# riffleito-KAP-REVB.net
KiCad netlist of a schematic drawn in EAGLE
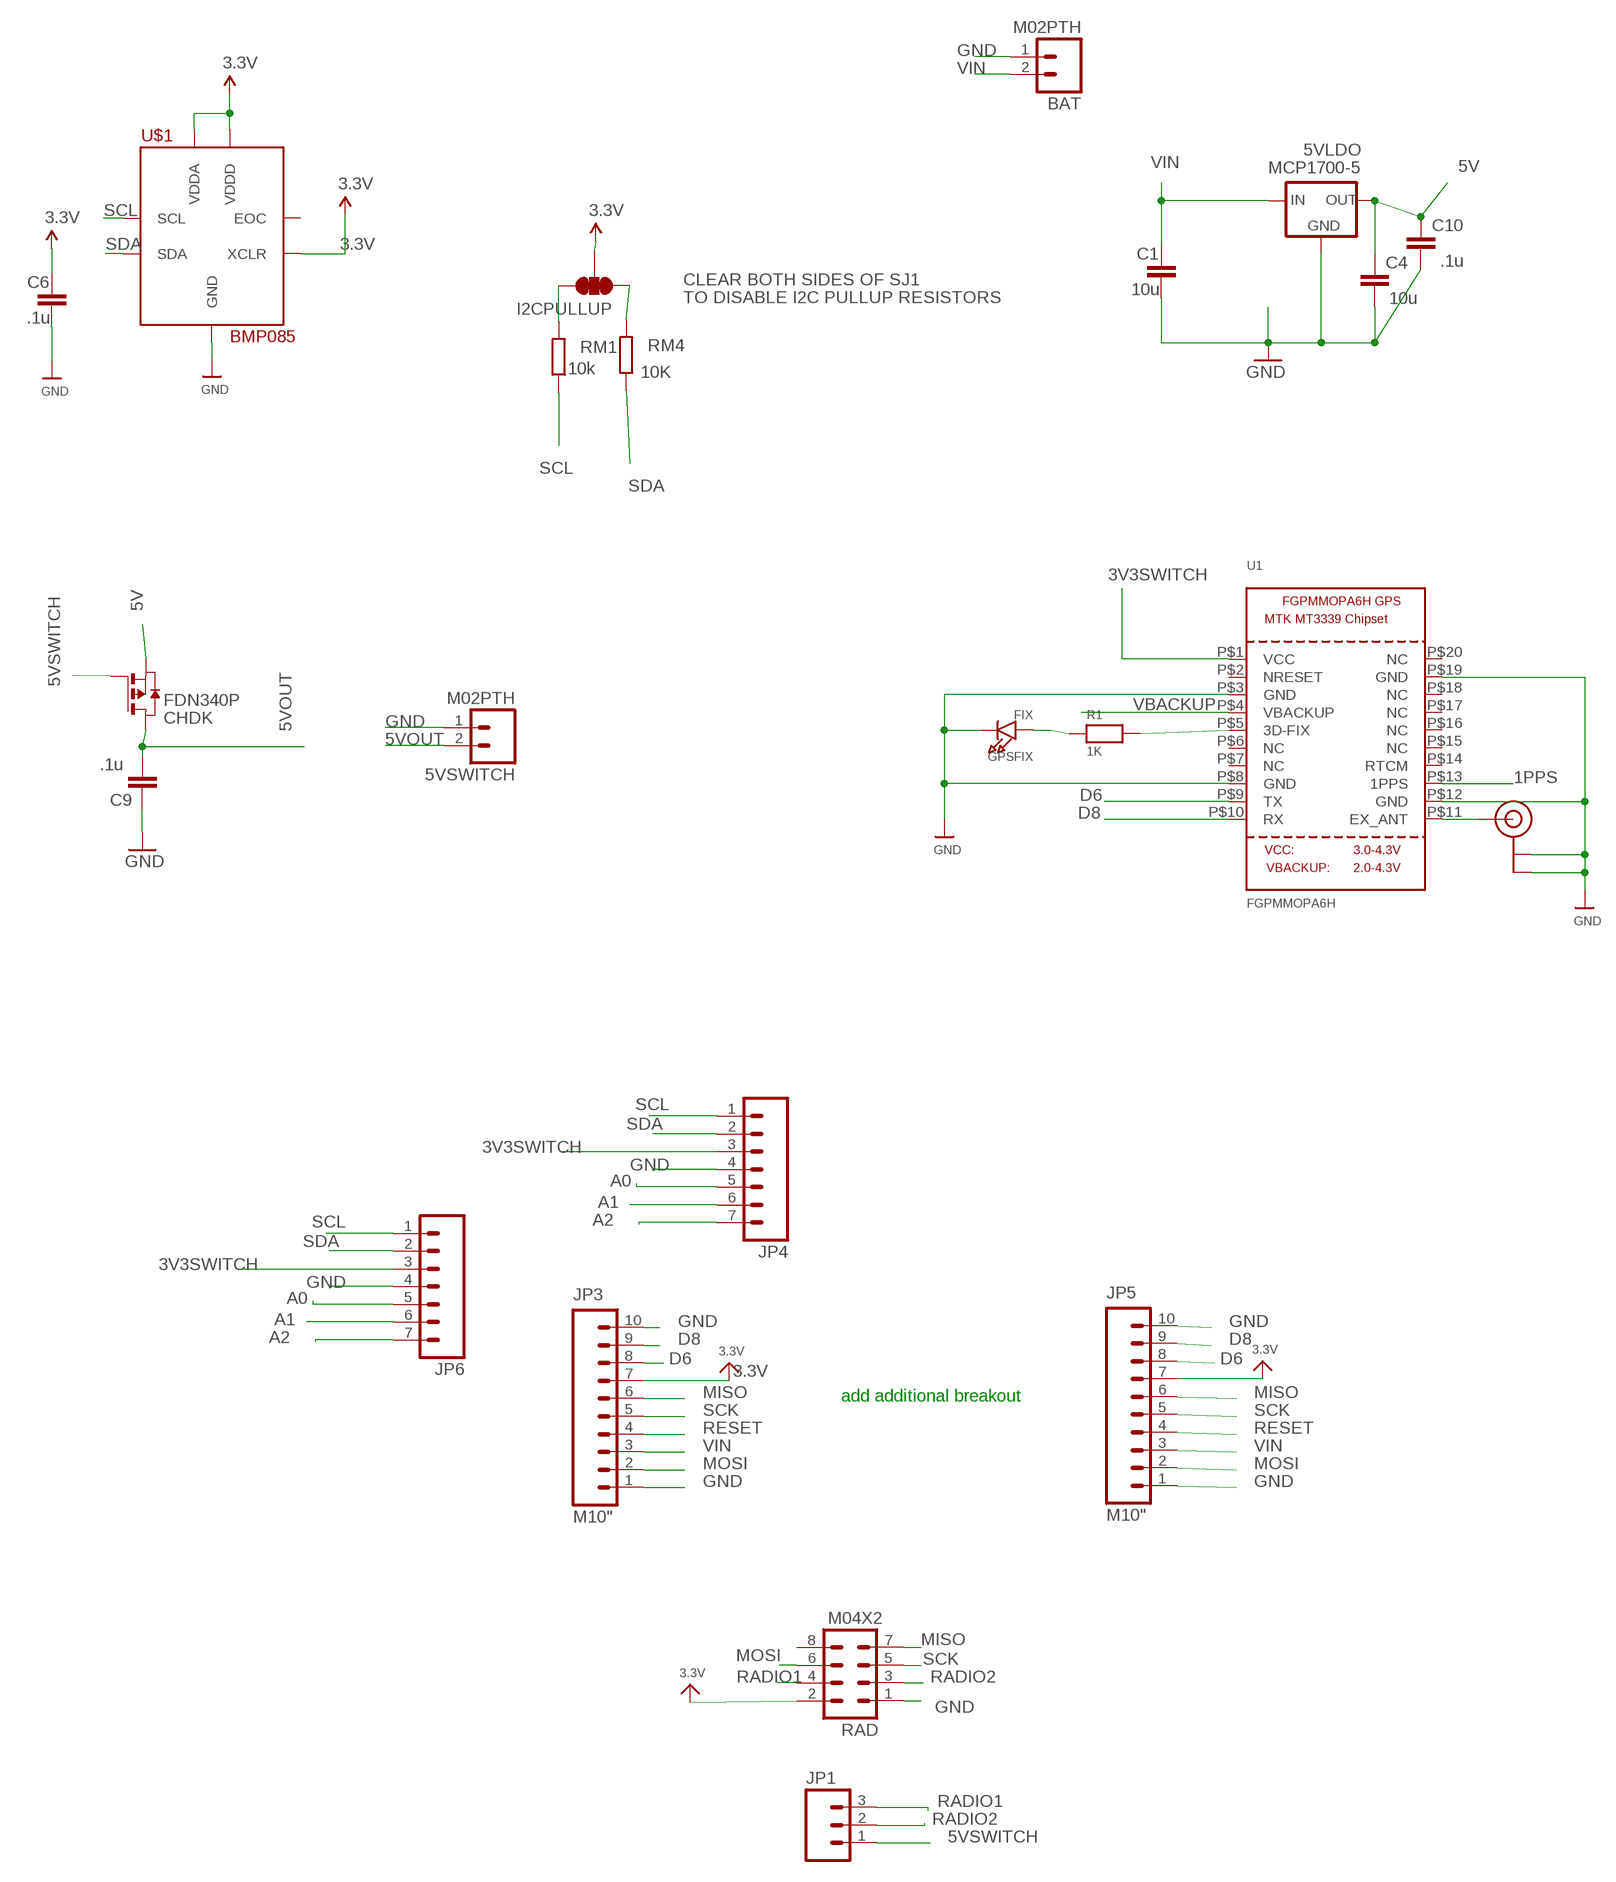
[diagram p0: schematic, sheet 1]

(export (version "E")
  (design (tool "Eeschema 10.0.6"))
  (components
    (comp (ref "5VLDO")
      (value "MCP1700-5")
      (footprint "eagle-import:SOT23")
      (libsource (lib "eagle-import") (part "MCP1700SOT233"))
    )
    (comp (ref "5VSWITCH")
      (value "M02PTH")
      (footprint "eagle-import:1X02")
      (libsource (lib "eagle-import") (part "M02PTH"))
    )
    (comp (ref "BAT")
      (value "M02PTH")
      (footprint "eagle-import:1X02")
      (libsource (lib "eagle-import") (part "M02PTH"))
    )
    (comp (ref "C1")
      (value "10u")
      (footprint "eagle-import:C0805")
      (libsource (lib "eagle-import") (part "C-EUC0805"))
    )
    (comp (ref "C4")
      (value "10u")
      (footprint "eagle-import:C0805")
      (libsource (lib "eagle-import") (part "C-EUC0805"))
    )
    (comp (ref "C6")
      (value ".1u")
      (footprint "eagle-import:C0805")
      (libsource (lib "eagle-import") (part "C-EUC0805"))
    )
    (comp (ref "C9")
      (value ".1u")
      (footprint "eagle-import:C0805")
      (libsource (lib "eagle-import") (part "C-EUC0805"))
    )
    (comp (ref "C10")
      (value ".1u")
      (footprint "eagle-import:C0805")
      (libsource (lib "eagle-import") (part "C-EUC0805"))
    )
    (comp (ref "CHDK")
      (value "FDN340P")
      (footprint "eagle-import:SOT-23")
      (libsource (lib "eagle-import") (part "PMOSSOT23"))
    )
    (comp (ref "GPSFIX")
      (value "FIX")
      (footprint "eagle-import:CHIPLED_0805")
      (libsource (lib "eagle-import") (part "LED0805"))
    )
    (comp (ref "I2CPULLUP")
      (value "SOLDERJUMPER_2WAYPASTE1&2&3")
      (footprint "eagle-import:SJ_3_PASTE1&2&3")
      (libsource (lib "eagle-import") (part "SOLDERJUMPER_2WAYPASTE1&2&3"))
    )
    (comp (ref "JP1")
      (value "M03PTH")
      (footprint "eagle-import:1X03")
      (libsource (lib "eagle-import") (part "M03PTH"))
    )
    (comp (ref "JP3")
      (value "M10\"")
      (footprint "eagle-import:1X10")
      (libsource (lib "eagle-import") (part "M10{dblquote}"))
    )
    (comp (ref "JP4")
      (value "M07")
      (footprint "eagle-import:1X07")
      (libsource (lib "eagle-import") (part "M07"))
    )
    (comp (ref "JP5")
      (value "M10\"")
      (footprint "eagle-import:1X10")
      (libsource (lib "eagle-import") (part "M10{dblquote}"))
    )
    (comp (ref "JP6")
      (value "M07")
      (footprint "eagle-import:1X07")
      (libsource (lib "eagle-import") (part "M07"))
    )
    (comp (ref "R1")
      (value "1K")
      (footprint "eagle-import:0805")
      (libsource (lib "eagle-import") (part "RESISTOR0805"))
    )
    (comp (ref "RAD")
      (value "M04X2")
      (footprint "eagle-import:2X4")
      (libsource (lib "eagle-import") (part "M04X2"))
    )
    (comp (ref "RM1")
      (value "10k")
      (footprint "eagle-import:R0805")
      (libsource (lib "eagle-import") (part "R-EU_R0805"))
    )
    (comp (ref "RM4")
      (value "10K")
      (footprint "eagle-import:R0805")
      (libsource (lib "eagle-import") (part "R-EU_R0805"))
    )
    (comp (ref "U$1")
      (value "BMP085")
      (footprint "eagle-import:BMP085")
      (libsource (lib "eagle-import") (part "BMP085"))
    )
    (comp (ref "U$20")
      (value "U.FL")
      (footprint "eagle-import:U.FL")
      (libsource (lib "eagle-import") (part "U.FL"))
    )
    (comp (ref "U1")
      (value "FGPMMOPA6H")
      (footprint "eagle-import:FGPMMOPA6H")
      (libsource (lib "eagle-import") (part "GPS_FGPMMOPA6H"))
    )
  )
  (nets
    (net (code "1") (name "/1PPS") (class "Default")
      (node (ref "U1") (pin "P$13") (pinfunction "1PPS_P$13") (pintype "bidirectional"))
    )
    (net (code "2") (name "/3V3SWITCH") (class "Default")
      (node (ref "JP4") (pin "3") (pinfunction "3_3") (pintype "passive"))
      (node (ref "JP6") (pin "3") (pinfunction "3_3") (pintype "passive"))
      (node (ref "U1") (pin "P$1") (pinfunction "VCC_P$1") (pintype "bidirectional"))
    )
    (net (code "3") (name "/5V") (class "Default")
      (node (ref "5VLDO") (pin "2") (pinfunction "OUT_2") (pintype "passive"))
      (node (ref "C10") (pin "1") (pinfunction "1_1") (pintype "passive"))
      (node (ref "C4") (pin "1") (pinfunction "1_1") (pintype "passive"))
      (node (ref "CHDK") (pin "2") (pinfunction "S_2") (pintype "passive"))
    )
    (net (code "4") (name "/5VOUT") (class "Default")
      (node (ref "5VSWITCH") (pin "2") (pinfunction "2_2") (pintype "passive"))
      (node (ref "C9") (pin "2") (pinfunction "2_2") (pintype "passive"))
      (node (ref "CHDK") (pin "1") (pinfunction "D_1") (pintype "passive"))
    )
    (net (code "5") (name "/5VSWITCH") (class "Default")
      (node (ref "CHDK") (pin "3") (pinfunction "G_3") (pintype "passive"))
      (node (ref "JP1") (pin "1") (pinfunction "1_1") (pintype "passive"))
    )
    (net (code "6") (name "/A0") (class "Default")
      (node (ref "JP4") (pin "5") (pinfunction "5_5") (pintype "passive"))
      (node (ref "JP6") (pin "5") (pinfunction "5_5") (pintype "passive"))
    )
    (net (code "7") (name "/A1") (class "Default")
      (node (ref "JP4") (pin "6") (pinfunction "6_6") (pintype "passive"))
      (node (ref "JP6") (pin "6") (pinfunction "6_6") (pintype "passive"))
    )
    (net (code "8") (name "/A2") (class "Default")
      (node (ref "JP4") (pin "7") (pinfunction "7_7") (pintype "passive"))
      (node (ref "JP6") (pin "7") (pinfunction "7_7") (pintype "passive"))
    )
    (net (code "9") (name "/D6") (class "Default")
      (node (ref "JP3") (pin "8") (pinfunction "8_8") (pintype "passive"))
      (node (ref "JP5") (pin "8") (pinfunction "8_8") (pintype "passive"))
      (node (ref "U1") (pin "P$9") (pinfunction "TX_P$9") (pintype "bidirectional"))
    )
    (net (code "10") (name "/D8") (class "Default")
      (node (ref "JP3") (pin "9") (pinfunction "9_9") (pintype "passive"))
      (node (ref "JP5") (pin "9") (pinfunction "9_9") (pintype "passive"))
      (node (ref "U1") (pin "P$10") (pinfunction "RX_P$10") (pintype "bidirectional"))
    )
    (net (code "11") (name "/MISO") (class "Default")
      (node (ref "JP3") (pin "6") (pinfunction "6_6") (pintype "passive"))
      (node (ref "JP5") (pin "6") (pinfunction "6_6") (pintype "passive"))
      (node (ref "RAD") (pin "7") (pinfunction "7_7") (pintype "passive"))
    )
    (net (code "12") (name "/MOSI") (class "Default")
      (node (ref "JP3") (pin "2") (pinfunction "2_2") (pintype "passive"))
      (node (ref "JP5") (pin "2") (pinfunction "2_2") (pintype "passive"))
      (node (ref "RAD") (pin "6") (pinfunction "6_6") (pintype "passive"))
    )
    (net (code "13") (name "/RADIO1") (class "Default")
      (node (ref "JP1") (pin "3") (pinfunction "3_3") (pintype "passive"))
      (node (ref "RAD") (pin "4") (pinfunction "4_4") (pintype "passive"))
    )
    (net (code "14") (name "/RADIO2") (class "Default")
      (node (ref "JP1") (pin "2") (pinfunction "2_2") (pintype "passive"))
      (node (ref "RAD") (pin "3") (pinfunction "3_3") (pintype "passive"))
    )
    (net (code "15") (name "/RESET") (class "Default")
      (node (ref "JP3") (pin "4") (pinfunction "4_4") (pintype "passive"))
      (node (ref "JP5") (pin "4") (pinfunction "4_4") (pintype "passive"))
    )
    (net (code "16") (name "/SCK") (class "Default")
      (node (ref "JP3") (pin "5") (pinfunction "5_5") (pintype "passive"))
      (node (ref "JP5") (pin "5") (pinfunction "5_5") (pintype "passive"))
      (node (ref "RAD") (pin "5") (pinfunction "5_5") (pintype "passive"))
    )
    (net (code "17") (name "/SCL") (class "Default")
      (node (ref "JP4") (pin "1") (pinfunction "1_1") (pintype "passive"))
      (node (ref "JP6") (pin "1") (pinfunction "1_1") (pintype "passive"))
      (node (ref "RM1") (pin "1") (pinfunction "1_1") (pintype "passive"))
      (node (ref "U$1") (pin "P$6") (pinfunction "SCL_P$6") (pintype "bidirectional"))
    )
    (net (code "18") (name "/SDA") (class "Default")
      (node (ref "JP4") (pin "2") (pinfunction "2_2") (pintype "passive"))
      (node (ref "JP6") (pin "2") (pinfunction "2_2") (pintype "passive"))
      (node (ref "RM4") (pin "1") (pinfunction "1_1") (pintype "passive"))
      (node (ref "U$1") (pin "P$7") (pinfunction "SDA_P$7") (pintype "bidirectional"))
    )
    (net (code "19") (name "/VBACKUP") (class "Default")
      (node (ref "U1") (pin "P$4") (pinfunction "VBACKUP_P$4") (pintype "bidirectional"))
    )
    (net (code "20") (name "/VIN") (class "Default")
      (node (ref "5VLDO") (pin "3") (pinfunction "IN_3") (pintype "input"))
      (node (ref "BAT") (pin "2") (pinfunction "2_2") (pintype "passive"))
      (node (ref "C1") (pin "1") (pinfunction "1_1") (pintype "passive"))
      (node (ref "JP3") (pin "3") (pinfunction "3_3") (pintype "passive"))
      (node (ref "JP5") (pin "3") (pinfunction "3_3") (pintype "passive"))
    )
    (net (code "21") (name "3.3V") (class "Default")
      (node (ref "C6") (pin "1") (pinfunction "1_1") (pintype "passive"))
      (node (ref "I2CPULLUP") (pin "2") (pinfunction "2_2") (pintype "passive"))
      (node (ref "JP3") (pin "7") (pinfunction "7_7") (pintype "passive"))
      (node (ref "JP5") (pin "7") (pinfunction "7_7") (pintype "passive"))
      (node (ref "RAD") (pin "2") (pinfunction "2_2") (pintype "passive"))
      (node (ref "U$1") (pin "P$3") (pinfunction "VDDA_P$3") (pintype "bidirectional"))
      (node (ref "U$1") (pin "P$4") (pinfunction "VDDD_P$4") (pintype "bidirectional"))
      (node (ref "U$1") (pin "P$8") (pinfunction "XCLR_P$8") (pintype "bidirectional"))
    )
    (net (code "22") (name "GND") (class "Default")
      (node (ref "5VLDO") (pin "1") (pinfunction "GND_1") (pintype "input"))
      (node (ref "5VSWITCH") (pin "1") (pinfunction "1_1") (pintype "passive"))
      (node (ref "BAT") (pin "1") (pinfunction "1_1") (pintype "passive"))
      (node (ref "C1") (pin "2") (pinfunction "2_2") (pintype "passive"))
      (node (ref "C10") (pin "2") (pinfunction "2_2") (pintype "passive"))
      (node (ref "C4") (pin "2") (pinfunction "2_2") (pintype "passive"))
      (node (ref "C6") (pin "2") (pinfunction "2_2") (pintype "passive"))
      (node (ref "C9") (pin "1") (pinfunction "1_1") (pintype "passive"))
      (node (ref "GPSFIX") (pin "C") (pinfunction "C_C") (pintype "passive"))
      (node (ref "JP3") (pin "1") (pinfunction "1_1") (pintype "passive"))
      (node (ref "JP3") (pin "10") (pinfunction "10_10") (pintype "passive"))
      (node (ref "JP4") (pin "4") (pinfunction "4_4") (pintype "passive"))
      (node (ref "JP5") (pin "1") (pinfunction "1_1") (pintype "passive"))
      (node (ref "JP5") (pin "10") (pinfunction "10_10") (pintype "passive"))
      (node (ref "JP6") (pin "4") (pinfunction "4_4") (pintype "passive"))
      (node (ref "RAD") (pin "1") (pinfunction "1_1") (pintype "passive"))
      (node (ref "U$1") (pin "P$1") (pinfunction "GND_P$1") (pintype "power_in"))
      (node (ref "U$20") (pin "P$1") (pinfunction "GND_P$1") (pintype "bidirectional"))
      (node (ref "U$20") (pin "P$2") (pinfunction "GND_P$2") (pintype "bidirectional"))
      (node (ref "U1") (pin "P$12") (pinfunction "GND_P$12") (pintype "bidirectional"))
      (node (ref "U1") (pin "P$19") (pinfunction "GND_P$19") (pintype "bidirectional"))
      (node (ref "U1") (pin "P$3") (pinfunction "GND_P$3") (pintype "bidirectional"))
      (node (ref "U1") (pin "P$8") (pinfunction "GND_P$8") (pintype "bidirectional"))
    )
    (net (code "23") (name "Net-(GPSFIX-PadA)") (class "Default")
      (node (ref "GPSFIX") (pin "A") (pinfunction "A_A") (pintype "passive"))
      (node (ref "R1") (pin "1") (pinfunction "1_1") (pintype "passive"))
    )
    (net (code "24") (name "Net-(I2CPULLUP-Pad1)") (class "Default")
      (node (ref "I2CPULLUP") (pin "1") (pinfunction "1_1") (pintype "passive"))
      (node (ref "RM4") (pin "2") (pinfunction "2_2") (pintype "passive"))
    )
    (net (code "25") (name "Net-(I2CPULLUP-Pad3)") (class "Default")
      (node (ref "I2CPULLUP") (pin "3") (pinfunction "3_3") (pintype "passive"))
      (node (ref "RM1") (pin "2") (pinfunction "2_2") (pintype "passive"))
    )
    (net (code "26") (name "Net-(U$20-SIGNAL)") (class "Default")
      (node (ref "U$20") (pin "P$3") (pinfunction "SIGNAL_P$3") (pintype "bidirectional"))
      (node (ref "U1") (pin "P$11") (pinfunction "EX_ANT_P$11") (pintype "bidirectional"))
    )
    (net (code "27") (name "Net-(U1-3D-FIX)") (class "Default")
      (node (ref "R1") (pin "2") (pinfunction "2_2") (pintype "passive"))
      (node (ref "U1") (pin "P$5") (pinfunction "3D-FIX_P$5") (pintype "bidirectional"))
    )
    (net (code "28") (name "unconnected-(RAD-Pad8)") (class "Default")
      (node (ref "RAD") (pin "8") (pinfunction "8_8") (pintype "passive"))
    )
    (net (code "29") (name "unconnected-(U$1-EOC-PadP$2)") (class "Default")
      (node (ref "U$1") (pin "P$2") (pinfunction "EOC_P$2") (pintype "bidirectional"))
    )
    (net (code "30") (name "unconnected-(U1-NC-PadP$6)") (class "Default")
      (node (ref "U1") (pin "P$6") (pinfunction "NC_P$6") (pintype "bidirectional"))
    )
    (net (code "31") (name "unconnected-(U1-NC-PadP$7)") (class "Default")
      (node (ref "U1") (pin "P$7") (pinfunction "NC_P$7") (pintype "bidirectional"))
    )
    (net (code "32") (name "unconnected-(U1-NC-PadP$15)") (class "Default")
      (node (ref "U1") (pin "P$15") (pinfunction "NC_P$15") (pintype "bidirectional"))
    )
    (net (code "33") (name "unconnected-(U1-NC-PadP$16)") (class "Default")
      (node (ref "U1") (pin "P$16") (pinfunction "NC_P$16") (pintype "bidirectional"))
    )
    (net (code "34") (name "unconnected-(U1-NC-PadP$17)") (class "Default")
      (node (ref "U1") (pin "P$17") (pinfunction "NC_P$17") (pintype "bidirectional"))
    )
    (net (code "35") (name "unconnected-(U1-NC-PadP$18)") (class "Default")
      (node (ref "U1") (pin "P$18") (pinfunction "NC_P$18") (pintype "bidirectional"))
    )
    (net (code "36") (name "unconnected-(U1-NC-PadP$20)") (class "Default")
      (node (ref "U1") (pin "P$20") (pinfunction "NC_P$20") (pintype "bidirectional"))
    )
    (net (code "37") (name "unconnected-(U1-NRESET-PadP$2)") (class "Default")
      (node (ref "U1") (pin "P$2") (pinfunction "NRESET_P$2") (pintype "bidirectional"))
    )
    (net (code "38") (name "unconnected-(U1-RTCM-PadP$14)") (class "Default")
      (node (ref "U1") (pin "P$14") (pinfunction "RTCM_P$14") (pintype "bidirectional"))
    )
  )
)
